# MUX.net
KiCad netlist of a schematic drawn in Altium Designer
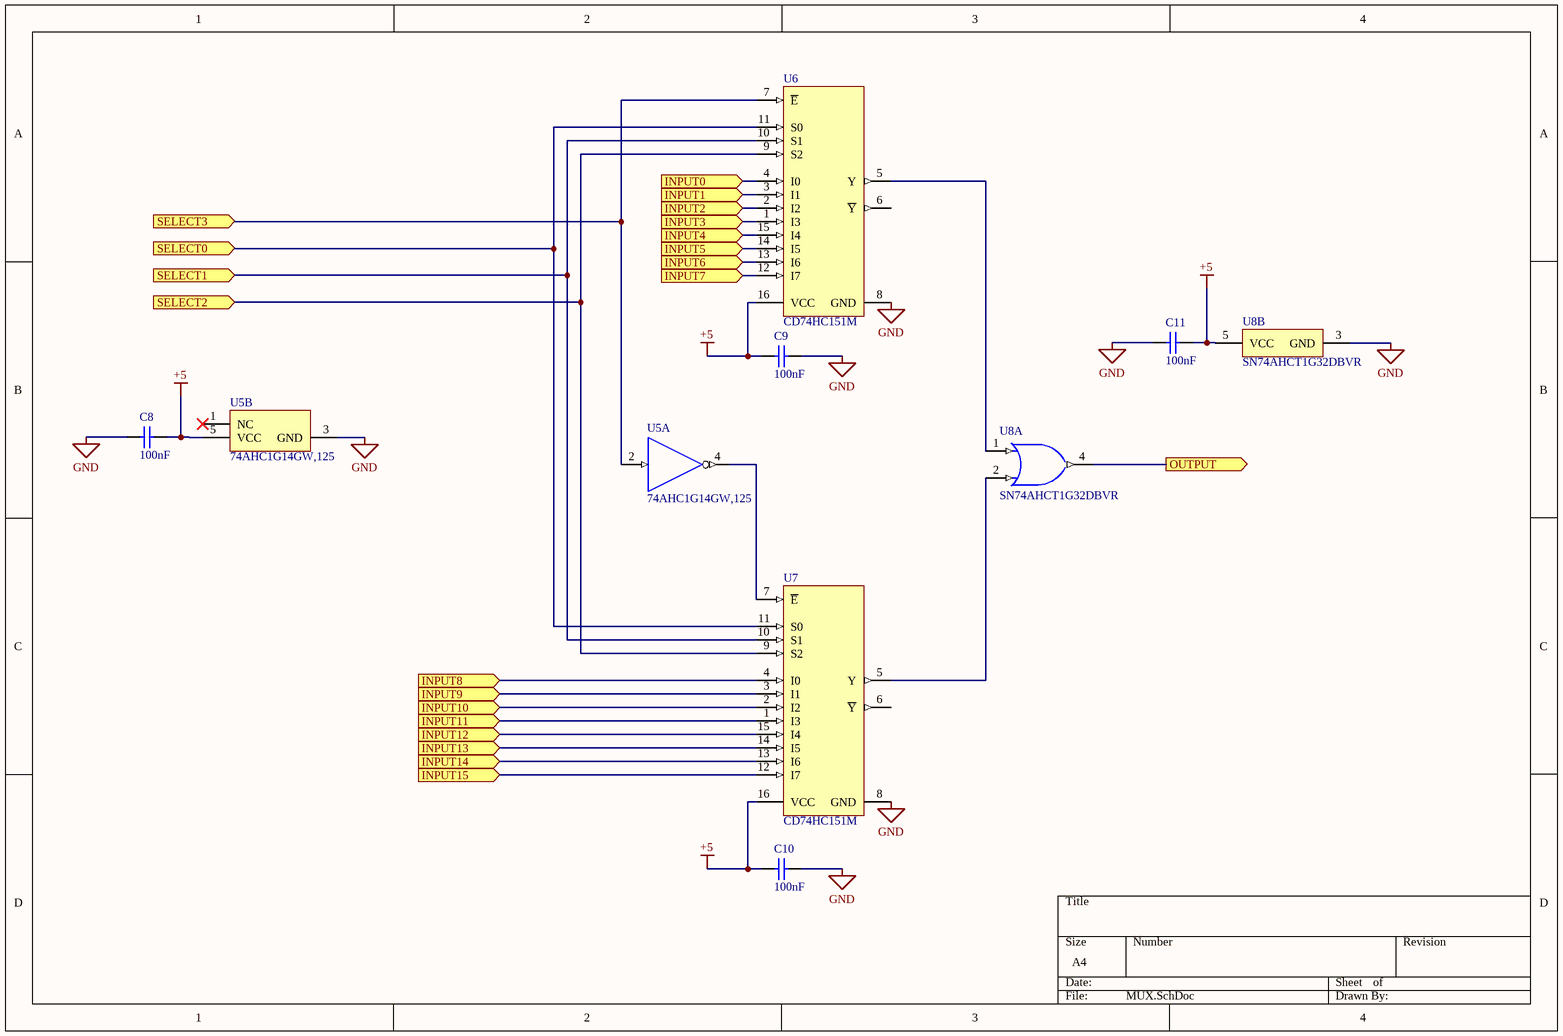
[diagram p0: MUX.SchDoc]

(export (version "E")
  (design (tool "Eeschema 10.0.6"))
  (components
    (comp (ref "C8")
      (value "100nF")
      (footprint "CAPC1206(3216)150_M")
      (description "CAP 100nF 250V ±10% 1206 (3216 Metric) Thickness 1.45mm SMD")
      (fields (field (name "TOLERANCE") "Â±10%"))
      (libsource (lib "Altium Content Vault") (part "CAP"))
    )
    (comp (ref "C9")
      (value "100nF")
      (footprint "CAPC1206(3216)150_M")
      (description "CAP 100nF 250V ±10% 1206 (3216 Metric) Thickness 1.45mm SMD")
      (fields (field (name "TOLERANCE") "Â±10%"))
      (libsource (lib "Altium Content Vault") (part "CAP"))
    )
    (comp (ref "C10")
      (value "100nF")
      (footprint "CAPC1206(3216)150_M")
      (description "CAP 100nF 250V ±10% 1206 (3216 Metric) Thickness 1.45mm SMD")
      (fields (field (name "TOLERANCE") "Â±10%"))
      (libsource (lib "Altium Content Vault") (part "CAP"))
    )
    (comp (ref "C11")
      (value "100nF")
      (footprint "CAPC1206(3216)150_M")
      (description "CAP 100nF 250V ±10% 1206 (3216 Metric) Thickness 1.45mm SMD")
      (fields (field (name "TOLERANCE") "Â±10%"))
      (libsource (lib "Altium Content Vault") (part "CAP"))
    )
    (comp (ref "U5")
      (value "74AHC1G14GW,125")
      (footprint "NXP-SOT353-1_L")
      (description "Inverting Schmitt Trigger, 1 uA, 2 to 5.5 V, -40 to 125 degC, 5-Pin TSSOP (SOT353-1), RoHS, Reel")
      (fields (field (name "MANUFACTURER") "NXP Semiconductors"))
      (libsource (lib "Altium Content Vault") (part "NXP-74AHCX1G14-5"))
    )
    (comp (ref "U6")
      (value "CD74HC151M")
      (footprint "D0016A_N")
      (description "High Speed CMOS Logic 8-Input Multiplexer, D0016A, TUBE")
      (fields
        (field (name "MANUFACTURER") "Texas Instruments")
        (field (name "GENERIC PART NUMBER") "CD74HC151")
      )
      (libsource (lib "Altium Content Vault") (part "TI-CDX4HCX151-16"))
    )
    (comp (ref "U7")
      (value "CD74HC151M")
      (footprint "D0016A_N")
      (description "High Speed CMOS Logic 8-Input Multiplexer, D0016A, TUBE")
      (fields
        (field (name "MANUFACTURER") "Texas Instruments")
        (field (name "GENERIC PART NUMBER") "CD74HC151")
      )
      (libsource (lib "Altium Content Vault") (part "TI-CDX4HCX151-16"))
    )
    (comp (ref "U8")
      (value "SN74AHCT1G32DBVR")
      (footprint "DBV0005A_M")
      (description "Single 2-Input Positive-OR Gate, DBV0005A, LARGE T&R")
      (fields
        (field (name "GENERIC PART NUMBER") "SN74AHCT1G32")
        (field (name "MANUFACTURER") "Texas Instruments")
      )
      (libsource (lib "Altium Content Vault") (part "TI-SN74XXX1X32-5"))
    )
  )
  (nets
    (net (code "1") (name "+5") (class "Default")
      (node (ref "C10") (pin "1") (pinfunction "1_1") (pintype "passive"))
      (node (ref "C11") (pin "2") (pinfunction "2_2") (pintype "passive"))
      (node (ref "C8") (pin "2") (pinfunction "2_2") (pintype "passive"))
      (node (ref "C9") (pin "1") (pinfunction "1_1") (pintype "passive"))
      (node (ref "U5") (pin "5") (pinfunction "VCC_5") (pintype "power_in"))
      (node (ref "U6") (pin "16") (pinfunction "VCC_16") (pintype "power_in"))
      (node (ref "U7") (pin "16") (pinfunction "VCC_16") (pintype "power_in"))
      (node (ref "U8") (pin "5") (pinfunction "VCC_5") (pintype "power_in"))
    )
    (net (code "2") (name "/INPUT0") (class "Default")
      (node (ref "U6") (pin "4") (pinfunction "I0_4") (pintype "input"))
    )
    (net (code "3") (name "/INPUT1") (class "Default")
      (node (ref "U6") (pin "3") (pinfunction "I1_3") (pintype "input"))
    )
    (net (code "4") (name "/INPUT2") (class "Default")
      (node (ref "U6") (pin "2") (pinfunction "I2_2") (pintype "input"))
    )
    (net (code "5") (name "/INPUT3") (class "Default")
      (node (ref "U6") (pin "1") (pinfunction "I3_1") (pintype "input"))
    )
    (net (code "6") (name "/INPUT4") (class "Default")
      (node (ref "U6") (pin "15") (pinfunction "I4_15") (pintype "input"))
    )
    (net (code "7") (name "/INPUT5") (class "Default")
      (node (ref "U6") (pin "14") (pinfunction "I5_14") (pintype "input"))
    )
    (net (code "8") (name "/INPUT6") (class "Default")
      (node (ref "U6") (pin "13") (pinfunction "I6_13") (pintype "input"))
    )
    (net (code "9") (name "/INPUT7") (class "Default")
      (node (ref "U6") (pin "12") (pinfunction "I7_12") (pintype "input"))
    )
    (net (code "10") (name "/INPUT8") (class "Default")
      (node (ref "U7") (pin "4") (pinfunction "I0_4") (pintype "input"))
    )
    (net (code "11") (name "/INPUT9") (class "Default")
      (node (ref "U7") (pin "3") (pinfunction "I1_3") (pintype "input"))
    )
    (net (code "12") (name "/INPUT10") (class "Default")
      (node (ref "U7") (pin "2") (pinfunction "I2_2") (pintype "input"))
    )
    (net (code "13") (name "/INPUT11") (class "Default")
      (node (ref "U7") (pin "1") (pinfunction "I3_1") (pintype "input"))
    )
    (net (code "14") (name "/INPUT12") (class "Default")
      (node (ref "U7") (pin "15") (pinfunction "I4_15") (pintype "input"))
    )
    (net (code "15") (name "/INPUT13") (class "Default")
      (node (ref "U7") (pin "14") (pinfunction "I5_14") (pintype "input"))
    )
    (net (code "16") (name "/INPUT14") (class "Default")
      (node (ref "U7") (pin "13") (pinfunction "I6_13") (pintype "input"))
    )
    (net (code "17") (name "/INPUT15") (class "Default")
      (node (ref "U7") (pin "12") (pinfunction "I7_12") (pintype "input"))
    )
    (net (code "18") (name "/OUTPUT") (class "Default")
      (node (ref "U8") (pin "4") (pinfunction "Y_4") (pintype "output"))
    )
    (net (code "19") (name "/SELECT0") (class "Default")
      (node (ref "U6") (pin "11") (pinfunction "S0_11") (pintype "input"))
      (node (ref "U7") (pin "11") (pinfunction "S0_11") (pintype "input"))
    )
    (net (code "20") (name "/SELECT1") (class "Default")
      (node (ref "U6") (pin "10") (pinfunction "S1_10") (pintype "input"))
      (node (ref "U7") (pin "10") (pinfunction "S1_10") (pintype "input"))
    )
    (net (code "21") (name "/SELECT2") (class "Default")
      (node (ref "U6") (pin "9") (pinfunction "S2_9") (pintype "input"))
      (node (ref "U7") (pin "9") (pinfunction "S2_9") (pintype "input"))
    )
    (net (code "22") (name "/SELECT3") (class "Default")
      (node (ref "U5") (pin "2") (pinfunction "A_2") (pintype "input"))
      (node (ref "U6") (pin "7") (pinfunction "~{E}_7") (pintype "input"))
    )
    (net (code "23") (name "GND") (class "Default")
      (node (ref "C10") (pin "2") (pinfunction "2_2") (pintype "passive"))
      (node (ref "C11") (pin "1") (pinfunction "1_1") (pintype "passive"))
      (node (ref "C8") (pin "1") (pinfunction "1_1") (pintype "passive"))
      (node (ref "C9") (pin "2") (pinfunction "2_2") (pintype "passive"))
      (node (ref "U5") (pin "3") (pinfunction "GND_3") (pintype "power_in"))
      (node (ref "U6") (pin "8") (pinfunction "GND_8") (pintype "power_in"))
      (node (ref "U7") (pin "8") (pinfunction "GND_8") (pintype "power_in"))
      (node (ref "U8") (pin "3") (pinfunction "GND_3") (pintype "power_in"))
    )
    (net (code "24") (name "Net-(U5A-~{Y})") (class "Default")
      (node (ref "U5") (pin "4") (pinfunction "~{Y}_4") (pintype "output"))
      (node (ref "U7") (pin "7") (pinfunction "~{E}_7") (pintype "input"))
    )
    (net (code "25") (name "Net-(U6-Y)") (class "Default")
      (node (ref "U6") (pin "5") (pinfunction "Y_5") (pintype "output"))
      (node (ref "U8") (pin "1") (pinfunction "A_1") (pintype "input"))
    )
    (net (code "26") (name "Net-(U7-Y)") (class "Default")
      (node (ref "U7") (pin "5") (pinfunction "Y_5") (pintype "output"))
      (node (ref "U8") (pin "2") (pinfunction "B_2") (pintype "input"))
    )
    (net (code "27") (name "unconnected-(U5B-NC-Pad1)") (class "Default")
      (node (ref "U5") (pin "1") (pinfunction "NC_1") (pintype "passive+no_connect"))
    )
    (net (code "28") (name "unconnected-(U6-~{Y}-Pad6)") (class "Default")
      (node (ref "U6") (pin "6") (pinfunction "~{Y}_6") (pintype "output"))
    )
    (net (code "29") (name "unconnected-(U7-~{Y}-Pad6)") (class "Default")
      (node (ref "U7") (pin "6") (pinfunction "~{Y}_6") (pintype "output"))
    )
  )
)
